# supply.net
KiCad netlist of a schematic drawn in Altium Designer
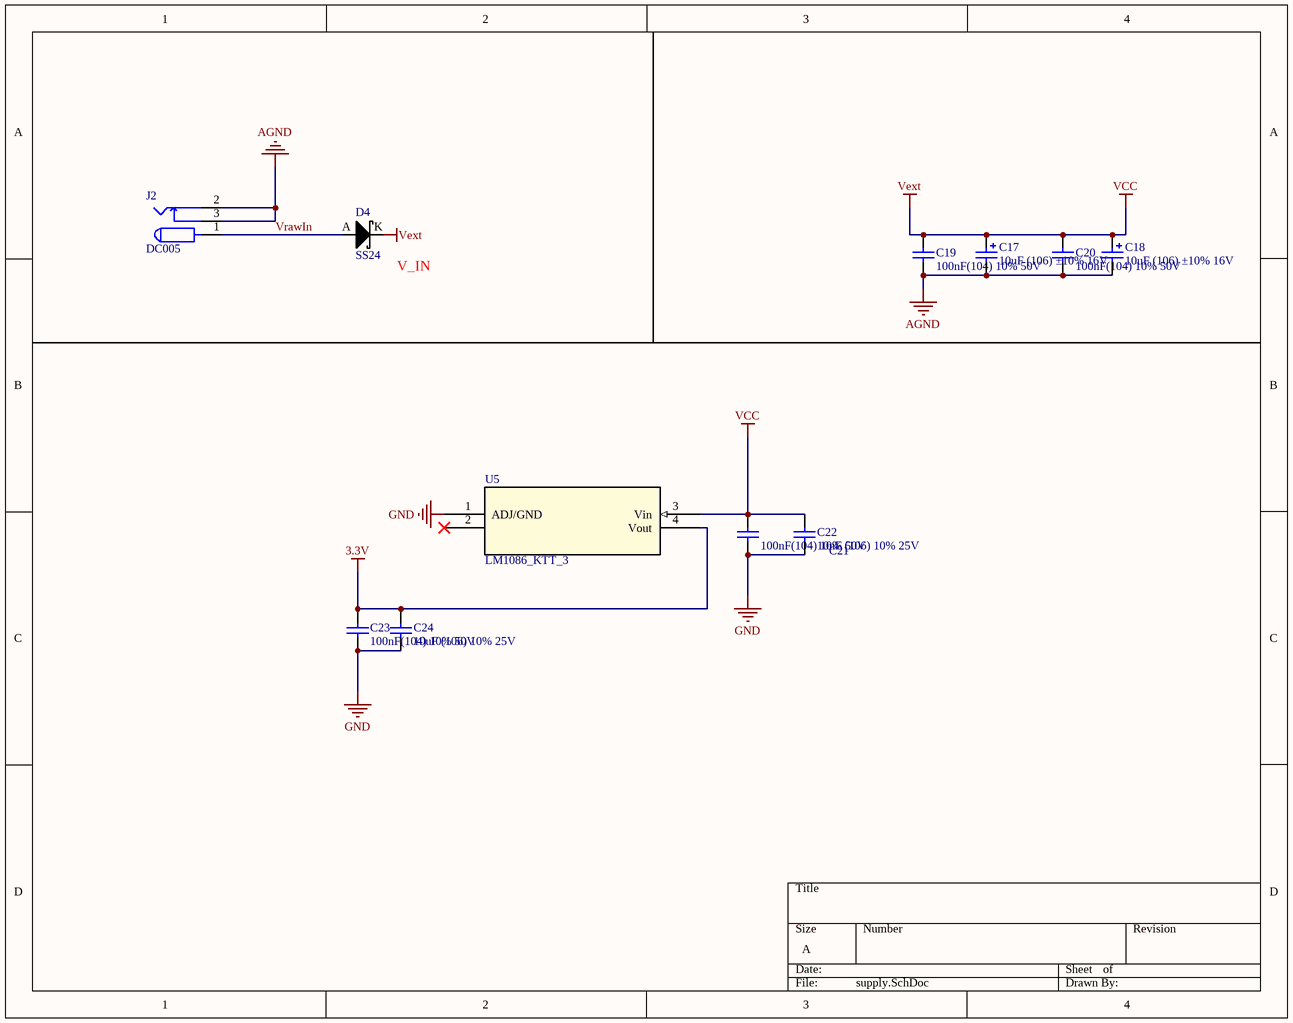
[diagram p0: supply.SchDoc]

(export (version "E")
  (design (tool "Eeschema 10.0.6"))
  (components
    (comp (ref "C17")
      (value "10uF (106) ±10% 16V")
      (footprint "CASE-A_3216")
      (description "钽电容")
      (libsource (lib "Cap") (part "3216 10uF (106) 10% 16V"))
    )
    (comp (ref "C18")
      (value "10uF (106) ±10% 16V")
      (footprint "CASE-A_3216")
      (description "钽电容")
      (libsource (lib "Cap") (part "3216 10uF (106) 10% 16V"))
    )
    (comp (ref "C19")
      (value "100nF(104) 10% 50V")
      (footprint "0805_C")
      (description "贴片电容")
      (libsource (lib "Cap") (part "0805 100nF(104) 10% 50V"))
    )
    (comp (ref "C20")
      (value "100nF(104) 10% 50V")
      (footprint "0805_C")
      (description "贴片电容")
      (libsource (lib "Cap") (part "0805 100nF(104) 10% 50V"))
    )
    (comp (ref "C21")
      (value "100nF(104) 10% 50V")
      (footprint "0805_C")
      (description "贴片电容")
      (libsource (lib "Cap") (part "0805 100nF(104) 10% 50V"))
    )
    (comp (ref "C22")
      (value "10uF (106) 10% 25V")
      (footprint "0805_C")
      (description "贴片电容")
      (libsource (lib "Cap") (part "0805 10uF (106) 10% 25V"))
    )
    (comp (ref "C23")
      (value "100nF(104) 10% 50V")
      (footprint "0805_C")
      (description "贴片电容")
      (libsource (lib "Cap") (part "0805 100nF(104) 10% 50V"))
    )
    (comp (ref "C24")
      (value "10uF (106) 10% 25V")
      (footprint "0805_C")
      (description "贴片电容")
      (libsource (lib "Cap") (part "0805 10uF (106) 10% 25V"))
    )
    (comp (ref "D4")
      (value "SS24")
      (footprint "SMB-DIODE-DO214AA")
      (description "SCHOTTKY DIODE")
      (fields (field (name "MANUFACTURER") "Fairchild Semiconductor"))
      (libsource (lib "Schlib1") (part "SS24"))
    )
    (comp (ref "J2") (value "DC005") (footprint "DC005") (libsource (lib "DC-connector") (part "DC005")))
    (comp (ref "U5")
      (value "LM1086_KTT_3")
      (footprint "TS3B")
      (description "Imported")
      (fields (field (name "PARTNUMBER") "LM1086CS-25"))
      (libsource (lib "LDO") (part "LM1086_KTT_3"))
    )
  )
  (nets
    (net (code "1") (name "/VrawIn") (class "Default")
      (node (ref "D4") (pin "A") (pinfunction "A_A") (pintype "passive"))
      (node (ref "J2") (pin "1") (pintype "passive"))
    )
    (net (code "2") (name "3.3V") (class "Default")
      (node (ref "C23") (pin "1") (pinfunction "1_1") (pintype "passive"))
      (node (ref "C24") (pin "2") (pinfunction "2_2") (pintype "passive"))
      (node (ref "U5") (pin "4") (pinfunction "Vout_4") (pintype "passive"))
    )
    (net (code "3") (name "AGND") (class "Default")
      (node (ref "C17") (pin "2") (pinfunction "2_2") (pintype "passive"))
      (node (ref "C18") (pin "2") (pinfunction "2_2") (pintype "passive"))
      (node (ref "C19") (pin "1") (pinfunction "1_1") (pintype "passive"))
      (node (ref "C20") (pin "1") (pinfunction "1_1") (pintype "passive"))
      (node (ref "J2") (pin "2") (pintype "passive"))
      (node (ref "J2") (pin "3") (pintype "passive"))
    )
    (net (code "4") (name "GND") (class "Default")
      (node (ref "C21") (pin "1") (pinfunction "1_1") (pintype "passive"))
      (node (ref "C22") (pin "1") (pinfunction "1_1") (pintype "passive"))
      (node (ref "C23") (pin "2") (pinfunction "2_2") (pintype "passive"))
      (node (ref "C24") (pin "1") (pinfunction "1_1") (pintype "passive"))
      (node (ref "U5") (pin "1") (pinfunction "ADJ/GND_1") (pintype "passive"))
    )
    (net (code "5") (name "VCC") (class "Default")
      (node (ref "C17") (pin "1") (pinfunction "1_1") (pintype "passive"))
      (node (ref "C18") (pin "1") (pinfunction "1_1") (pintype "passive"))
      (node (ref "C19") (pin "2") (pinfunction "2_2") (pintype "passive"))
      (node (ref "C20") (pin "2") (pinfunction "2_2") (pintype "passive"))
      (node (ref "C21") (pin "2") (pinfunction "2_2") (pintype "passive"))
      (node (ref "C22") (pin "2") (pinfunction "2_2") (pintype "passive"))
      (node (ref "D4") (pin "K") (pinfunction "K_K") (pintype "passive"))
      (node (ref "U5") (pin "3") (pinfunction "Vin_3") (pintype "input"))
    )
    (net (code "6") (name "unconnected-(U5-Vout-Pad2)") (class "Default")
      (node (ref "U5") (pin "2") (pinfunction "Vout_2") (pintype "passive+no_connect"))
    )
  )
)
